# DCDC-18V12V5A.net
KiCad netlist of a schematic drawn in EAGLE
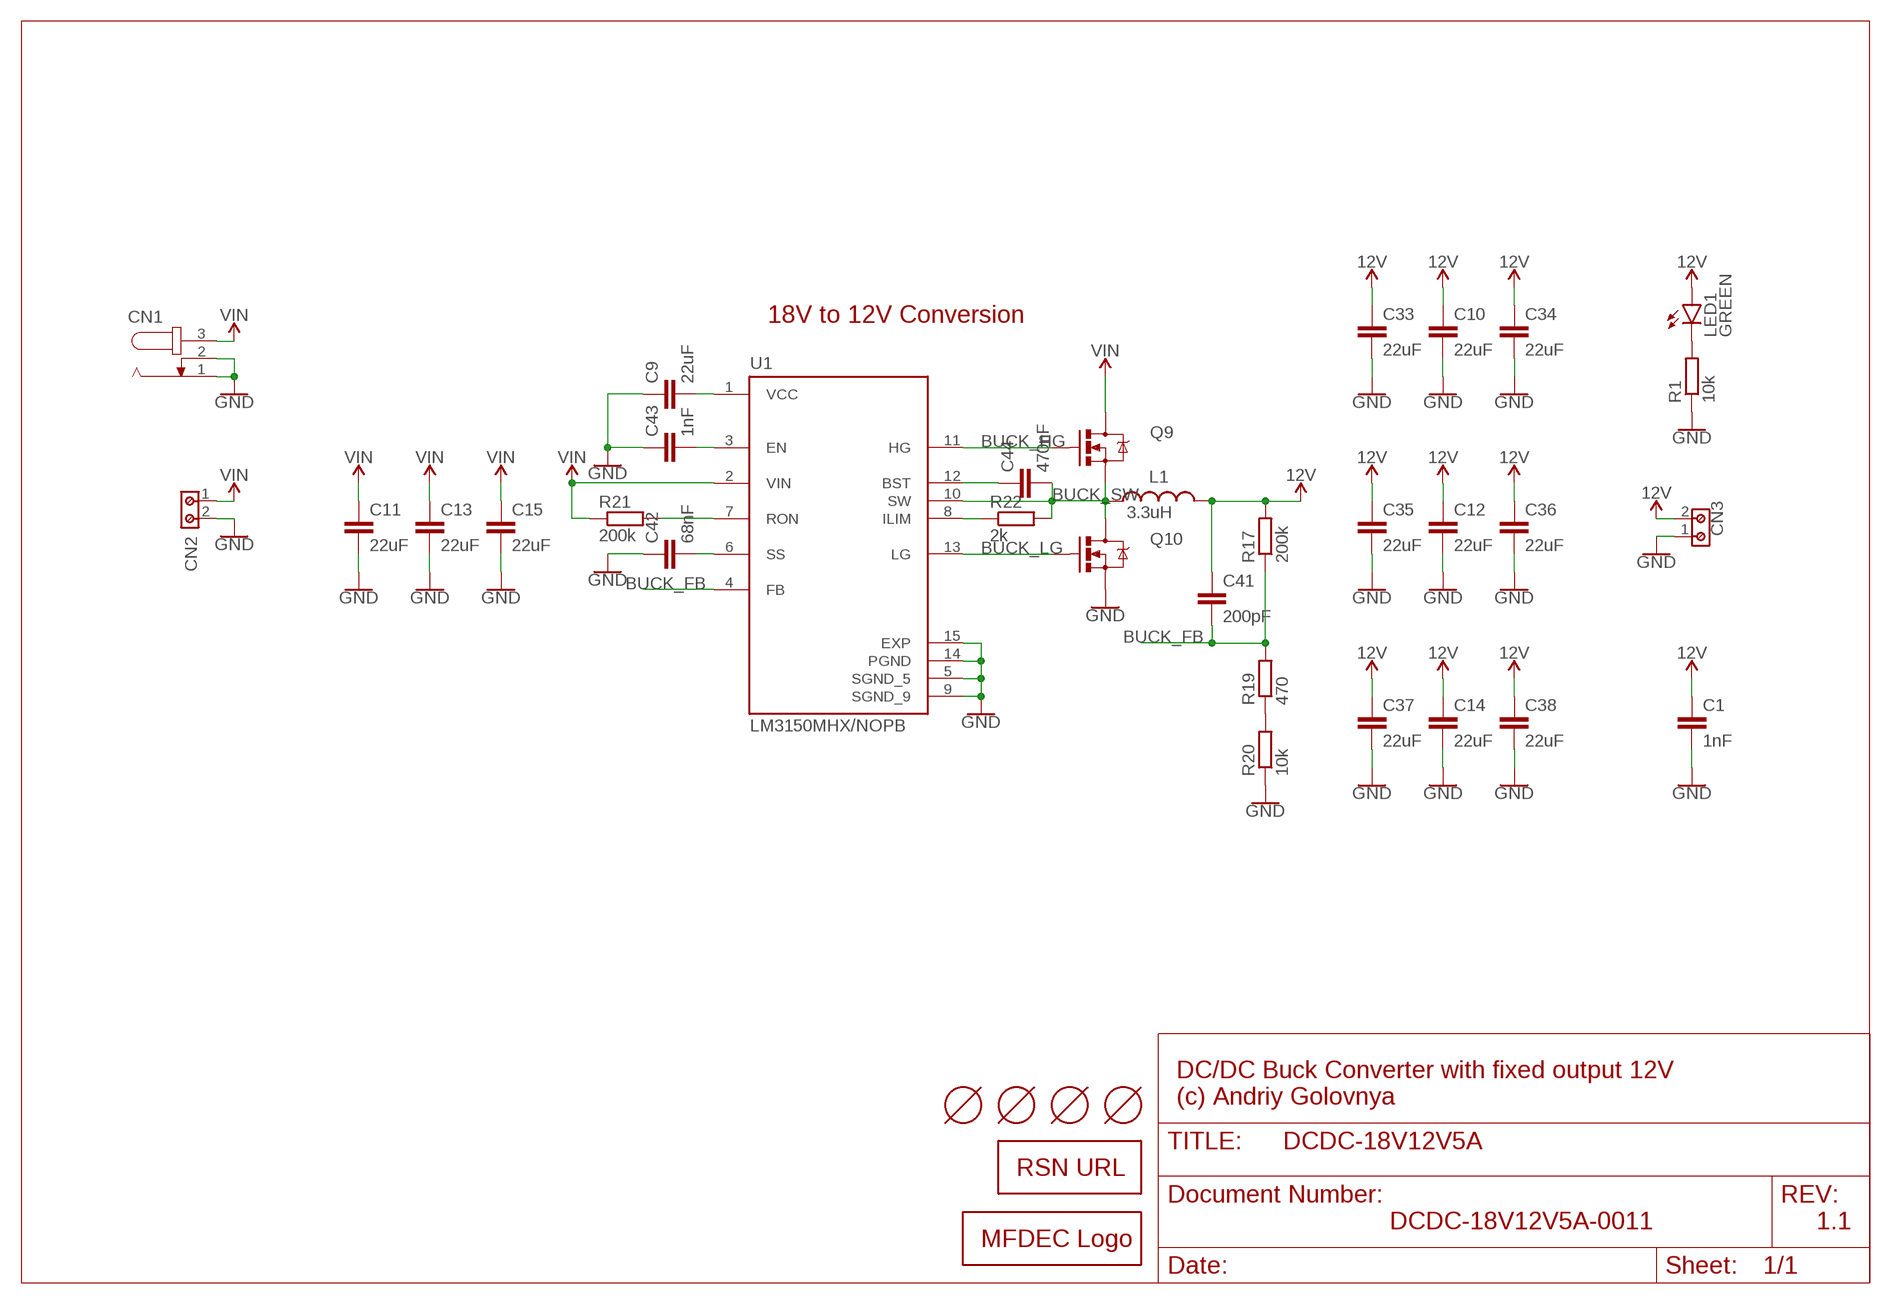
[diagram p0: schematic, sheet 1]

(export (version "E")
  (design (tool "Eeschema 10.0.6"))
  (components
    (comp (ref "C1")
      (value "1nF")
      (footprint "eagle-import:C0603K")
      (libsource (lib "eagle-import") (part "C-EUC0603K"))
    )
    (comp (ref "C9")
      (value "22uF")
      (footprint "eagle-import:C0805K")
      (libsource (lib "eagle-import") (part "C-EUC0805K"))
    )
    (comp (ref "C10")
      (value "22uF")
      (footprint "eagle-import:C0805K")
      (libsource (lib "eagle-import") (part "C-EUC0805K"))
    )
    (comp (ref "C11")
      (value "22uF")
      (footprint "eagle-import:C0805K")
      (libsource (lib "eagle-import") (part "C-EUC0805K"))
    )
    (comp (ref "C12")
      (value "22uF")
      (footprint "eagle-import:C0805K")
      (libsource (lib "eagle-import") (part "C-EUC0805K"))
    )
    (comp (ref "C13")
      (value "22uF")
      (footprint "eagle-import:C0805K")
      (libsource (lib "eagle-import") (part "C-EUC0805K"))
    )
    (comp (ref "C14")
      (value "22uF")
      (footprint "eagle-import:C0805K")
      (libsource (lib "eagle-import") (part "C-EUC0805K"))
    )
    (comp (ref "C15")
      (value "22uF")
      (footprint "eagle-import:C0805K")
      (libsource (lib "eagle-import") (part "C-EUC0805K"))
    )
    (comp (ref "C33")
      (value "22uF")
      (footprint "eagle-import:C0805K")
      (libsource (lib "eagle-import") (part "C-EUC0805K"))
    )
    (comp (ref "C34")
      (value "22uF")
      (footprint "eagle-import:C0805K")
      (libsource (lib "eagle-import") (part "C-EUC0805K"))
    )
    (comp (ref "C35")
      (value "22uF")
      (footprint "eagle-import:C0805K")
      (libsource (lib "eagle-import") (part "C-EUC0805K"))
    )
    (comp (ref "C36")
      (value "22uF")
      (footprint "eagle-import:C0805K")
      (libsource (lib "eagle-import") (part "C-EUC0805K"))
    )
    (comp (ref "C37")
      (value "22uF")
      (footprint "eagle-import:C0805K")
      (libsource (lib "eagle-import") (part "C-EUC0805K"))
    )
    (comp (ref "C38")
      (value "22uF")
      (footprint "eagle-import:C0805K")
      (libsource (lib "eagle-import") (part "C-EUC0805K"))
    )
    (comp (ref "C41")
      (value "200pF")
      (footprint "eagle-import:C0603K")
      (libsource (lib "eagle-import") (part "C-EUC0603K"))
    )
    (comp (ref "C42")
      (value "68nF")
      (footprint "eagle-import:C0603K")
      (libsource (lib "eagle-import") (part "C-EUC0603K"))
    )
    (comp (ref "C43")
      (value "1nF")
      (footprint "eagle-import:C0603K")
      (libsource (lib "eagle-import") (part "C-EUC0603K"))
    )
    (comp (ref "C44")
      (value "470nF")
      (footprint "eagle-import:C0603K")
      (libsource (lib "eagle-import") (part "C-EUC0603K"))
    )
    (comp (ref "CN1")
      (value "JACK-PLUG1")
      (footprint "eagle-import:SPC4078")
      (libsource (lib "eagle-import") (part "JACK-PLUG1"))
    )
    (comp (ref "CN2")
      (value "691213510002")
      (footprint "eagle-import:691213510002")
      (libsource (lib "eagle-import") (part "691213510002"))
    )
    (comp (ref "CN3")
      (value "691213510002")
      (footprint "eagle-import:691213510002")
      (libsource (lib "eagle-import") (part "691213510002"))
    )
    (comp (ref "HOLE1")
      (value "TOOLINGHOLE")
      (footprint "eagle-import:TOOLING-HOLE")
      (libsource (lib "eagle-import") (part "TOOLINGHOLE"))
    )
    (comp (ref "HOLE2")
      (value "TOOLINGHOLE")
      (footprint "eagle-import:TOOLING-HOLE")
      (libsource (lib "eagle-import") (part "TOOLINGHOLE"))
    )
    (comp (ref "HOLE3")
      (value "TOOLINGHOLE")
      (footprint "eagle-import:TOOLING-HOLE")
      (libsource (lib "eagle-import") (part "TOOLINGHOLE"))
    )
    (comp (ref "HOLE4")
      (value "TOOLINGHOLE")
      (footprint "eagle-import:TOOLING-HOLE")
      (libsource (lib "eagle-import") (part "TOOLINGHOLE"))
    )
    (comp (ref "L1")
      (value "3.3uH")
      (footprint "eagle-import:WE-CHSA_1011")
      (libsource (lib "eagle-import") (part "WE-CHSA_1011_7843330330"))
    )
    (comp (ref "LED1")
      (value "GREEN")
      (footprint "eagle-import:SML0603")
      (libsource (lib "eagle-import") (part "LEDSML0603"))
    )
    (comp (ref "LOGO1")
      (value "RSNURL_QR_8MM")
      (footprint "eagle-import:RSNURL_QR_8MM")
      (libsource (lib "eagle-import") (part "RSNURL_QR_8MM"))
    )
    (comp (ref "LOGO2")
      (value "MFDECLOGO_L_10MM")
      (footprint "eagle-import:MFDEC_L_10MM")
      (libsource (lib "eagle-import") (part "MFDECLOGO_L_10MM"))
    )
    (comp (ref "Q9")
      (value "NMOSFET")
      (footprint "eagle-import:DPAK")
      (libsource (lib "eagle-import") (part "MOSFET-NCHANNELFDD8780"))
    )
    (comp (ref "Q10")
      (value "NMOSFET")
      (footprint "eagle-import:DPAK")
      (libsource (lib "eagle-import") (part "MOSFET-NCHANNELFDD8780"))
    )
    (comp (ref "R1")
      (value "10k")
      (footprint "eagle-import:R0603")
      (libsource (lib "eagle-import") (part "R-EU_R0603"))
    )
    (comp (ref "R17")
      (value "200k")
      (footprint "eagle-import:R0603")
      (libsource (lib "eagle-import") (part "R-EU_R0603"))
    )
    (comp (ref "R19")
      (value "470")
      (footprint "eagle-import:R0603")
      (libsource (lib "eagle-import") (part "R-EU_R0603"))
    )
    (comp (ref "R20")
      (value "10k")
      (footprint "eagle-import:R0603")
      (libsource (lib "eagle-import") (part "R-EU_R0603"))
    )
    (comp (ref "R21")
      (value "200k")
      (footprint "eagle-import:R0603")
      (libsource (lib "eagle-import") (part "R-EU_R0603"))
    )
    (comp (ref "R22")
      (value "2k")
      (footprint "eagle-import:R0603")
      (libsource (lib "eagle-import") (part "R-EU_R0603"))
    )
    (comp (ref "U1")
      (value "LM3150MHX/NOPB")
      (footprint "eagle-import:SOP65P640X110-15N")
      (fields (field (name "MF") "Texas Instruments"))
      (libsource (lib "eagle-import") (part "LM3150MHX/NOPB"))
    )
  )
  (nets
    (net (code "1") (name "/BUCK_FB") (class "Default")
      (node (ref "C41") (pin "2") (pinfunction "2_2") (pintype "passive"))
      (node (ref "R17") (pin "1") (pinfunction "1_1") (pintype "passive"))
      (node (ref "R19") (pin "2") (pinfunction "2_2") (pintype "passive"))
      (node (ref "U1") (pin "4") (pinfunction "FB_4") (pintype "input"))
    )
    (net (code "2") (name "/BUCK_HG") (class "Default")
      (node (ref "Q9") (pin "1") (pinfunction "G_1") (pintype "passive"))
      (node (ref "U1") (pin "11") (pinfunction "HG_11") (pintype "output"))
    )
    (net (code "3") (name "/BUCK_LG") (class "Default")
      (node (ref "Q10") (pin "1") (pinfunction "G_1") (pintype "passive"))
      (node (ref "U1") (pin "13") (pinfunction "LG_13") (pintype "output"))
    )
    (net (code "4") (name "/BUCK_SW") (class "Default")
      (node (ref "C44") (pin "2") (pinfunction "2_2") (pintype "passive"))
      (node (ref "L1") (pin "1") (pinfunction "1_1") (pintype "passive"))
      (node (ref "Q10") (pin "4") (pinfunction "D_4") (pintype "passive"))
      (node (ref "Q9") (pin "3") (pinfunction "S_3") (pintype "passive"))
      (node (ref "R22") (pin "2") (pinfunction "2_2") (pintype "passive"))
      (node (ref "U1") (pin "10") (pinfunction "SW_10") (pintype "output"))
    )
    (net (code "5") (name "12V") (class "Default")
      (node (ref "C1") (pin "1") (pinfunction "1_1") (pintype "passive"))
      (node (ref "C10") (pin "1") (pinfunction "1_1") (pintype "passive"))
      (node (ref "C12") (pin "1") (pinfunction "1_1") (pintype "passive"))
      (node (ref "C14") (pin "1") (pinfunction "1_1") (pintype "passive"))
      (node (ref "C33") (pin "1") (pinfunction "1_1") (pintype "passive"))
      (node (ref "C34") (pin "1") (pinfunction "1_1") (pintype "passive"))
      (node (ref "C35") (pin "1") (pinfunction "1_1") (pintype "passive"))
      (node (ref "C36") (pin "1") (pinfunction "1_1") (pintype "passive"))
      (node (ref "C37") (pin "1") (pinfunction "1_1") (pintype "passive"))
      (node (ref "C38") (pin "1") (pinfunction "1_1") (pintype "passive"))
      (node (ref "C41") (pin "1") (pinfunction "1_1") (pintype "passive"))
      (node (ref "CN3") (pin "2") (pinfunction "2_2") (pintype "passive"))
      (node (ref "L1") (pin "2") (pinfunction "2_2") (pintype "passive"))
      (node (ref "LED1") (pin "A") (pinfunction "A_A") (pintype "passive"))
      (node (ref "R17") (pin "2") (pinfunction "2_2") (pintype "passive"))
    )
    (net (code "6") (name "GND") (class "Default")
      (node (ref "C1") (pin "2") (pinfunction "2_2") (pintype "passive"))
      (node (ref "C10") (pin "2") (pinfunction "2_2") (pintype "passive"))
      (node (ref "C11") (pin "2") (pinfunction "2_2") (pintype "passive"))
      (node (ref "C12") (pin "2") (pinfunction "2_2") (pintype "passive"))
      (node (ref "C13") (pin "2") (pinfunction "2_2") (pintype "passive"))
      (node (ref "C14") (pin "2") (pinfunction "2_2") (pintype "passive"))
      (node (ref "C15") (pin "2") (pinfunction "2_2") (pintype "passive"))
      (node (ref "C33") (pin "2") (pinfunction "2_2") (pintype "passive"))
      (node (ref "C34") (pin "2") (pinfunction "2_2") (pintype "passive"))
      (node (ref "C35") (pin "2") (pinfunction "2_2") (pintype "passive"))
      (node (ref "C36") (pin "2") (pinfunction "2_2") (pintype "passive"))
      (node (ref "C37") (pin "2") (pinfunction "2_2") (pintype "passive"))
      (node (ref "C38") (pin "2") (pinfunction "2_2") (pintype "passive"))
      (node (ref "C42") (pin "1") (pinfunction "1_1") (pintype "passive"))
      (node (ref "C43") (pin "1") (pinfunction "1_1") (pintype "passive"))
      (node (ref "C9") (pin "1") (pinfunction "1_1") (pintype "passive"))
      (node (ref "CN1") (pin "1") (pinfunction "1_1") (pintype "passive"))
      (node (ref "CN1") (pin "2") (pinfunction "2_2") (pintype "passive"))
      (node (ref "CN2") (pin "2") (pinfunction "2_2") (pintype "passive"))
      (node (ref "CN3") (pin "1") (pinfunction "1_1") (pintype "passive"))
      (node (ref "Q10") (pin "3") (pinfunction "S_3") (pintype "passive"))
      (node (ref "R1") (pin "1") (pinfunction "1_1") (pintype "passive"))
      (node (ref "R20") (pin "1") (pinfunction "1_1") (pintype "passive"))
      (node (ref "U1") (pin "14") (pinfunction "PGND_14") (pintype "power_in"))
      (node (ref "U1") (pin "15") (pinfunction "EXP_15") (pintype "power_in"))
      (node (ref "U1") (pin "5") (pinfunction "SGND_5_5") (pintype "power_in"))
      (node (ref "U1") (pin "9") (pinfunction "SGND_9_9") (pintype "power_in"))
    )
    (net (code "7") (name "Net-(LED1-PadC)") (class "Default")
      (node (ref "LED1") (pin "C") (pinfunction "C_C") (pintype "passive"))
      (node (ref "R1") (pin "2") (pinfunction "2_2") (pintype "passive"))
    )
    (net (code "8") (name "Net-(R19-Pad1)") (class "Default")
      (node (ref "R19") (pin "1") (pinfunction "1_1") (pintype "passive"))
      (node (ref "R20") (pin "2") (pinfunction "2_2") (pintype "passive"))
    )
    (net (code "9") (name "Net-(U1-BST)") (class "Default")
      (node (ref "C44") (pin "1") (pinfunction "1_1") (pintype "passive"))
      (node (ref "U1") (pin "12") (pinfunction "BST_12") (pintype "passive"))
    )
    (net (code "10") (name "Net-(U1-EN)") (class "Default")
      (node (ref "C43") (pin "2") (pinfunction "2_2") (pintype "passive"))
      (node (ref "U1") (pin "3") (pinfunction "EN_3") (pintype "input"))
    )
    (net (code "11") (name "Net-(U1-ILIM)") (class "Default")
      (node (ref "R22") (pin "1") (pinfunction "1_1") (pintype "passive"))
      (node (ref "U1") (pin "8") (pinfunction "ILIM_8") (pintype "passive"))
    )
    (net (code "12") (name "Net-(U1-RON)") (class "Default")
      (node (ref "R21") (pin "2") (pinfunction "2_2") (pintype "passive"))
      (node (ref "U1") (pin "7") (pinfunction "RON_7") (pintype "input"))
    )
    (net (code "13") (name "Net-(U1-SS)") (class "Default")
      (node (ref "C42") (pin "2") (pinfunction "2_2") (pintype "passive"))
      (node (ref "U1") (pin "6") (pinfunction "SS_6") (pintype "input"))
    )
    (net (code "14") (name "Net-(U1-VCC)") (class "Default")
      (node (ref "C9") (pin "2") (pinfunction "2_2") (pintype "passive"))
      (node (ref "U1") (pin "1") (pinfunction "VCC_1") (pintype "power_in"))
    )
    (net (code "15") (name "VIN") (class "Default")
      (node (ref "C11") (pin "1") (pinfunction "1_1") (pintype "passive"))
      (node (ref "C13") (pin "1") (pinfunction "1_1") (pintype "passive"))
      (node (ref "C15") (pin "1") (pinfunction "1_1") (pintype "passive"))
      (node (ref "CN1") (pin "3") (pinfunction "3_3") (pintype "passive"))
      (node (ref "CN2") (pin "1") (pinfunction "1_1") (pintype "passive"))
      (node (ref "Q9") (pin "4") (pinfunction "D_4") (pintype "passive"))
      (node (ref "R21") (pin "1") (pinfunction "1_1") (pintype "passive"))
      (node (ref "U1") (pin "2") (pinfunction "VIN_2") (pintype "input"))
    )
  )
)
